# EasyEDA_H-O-A_Switch_Plug.net
KiCad netlist of a schematic drawn in EasyEDA
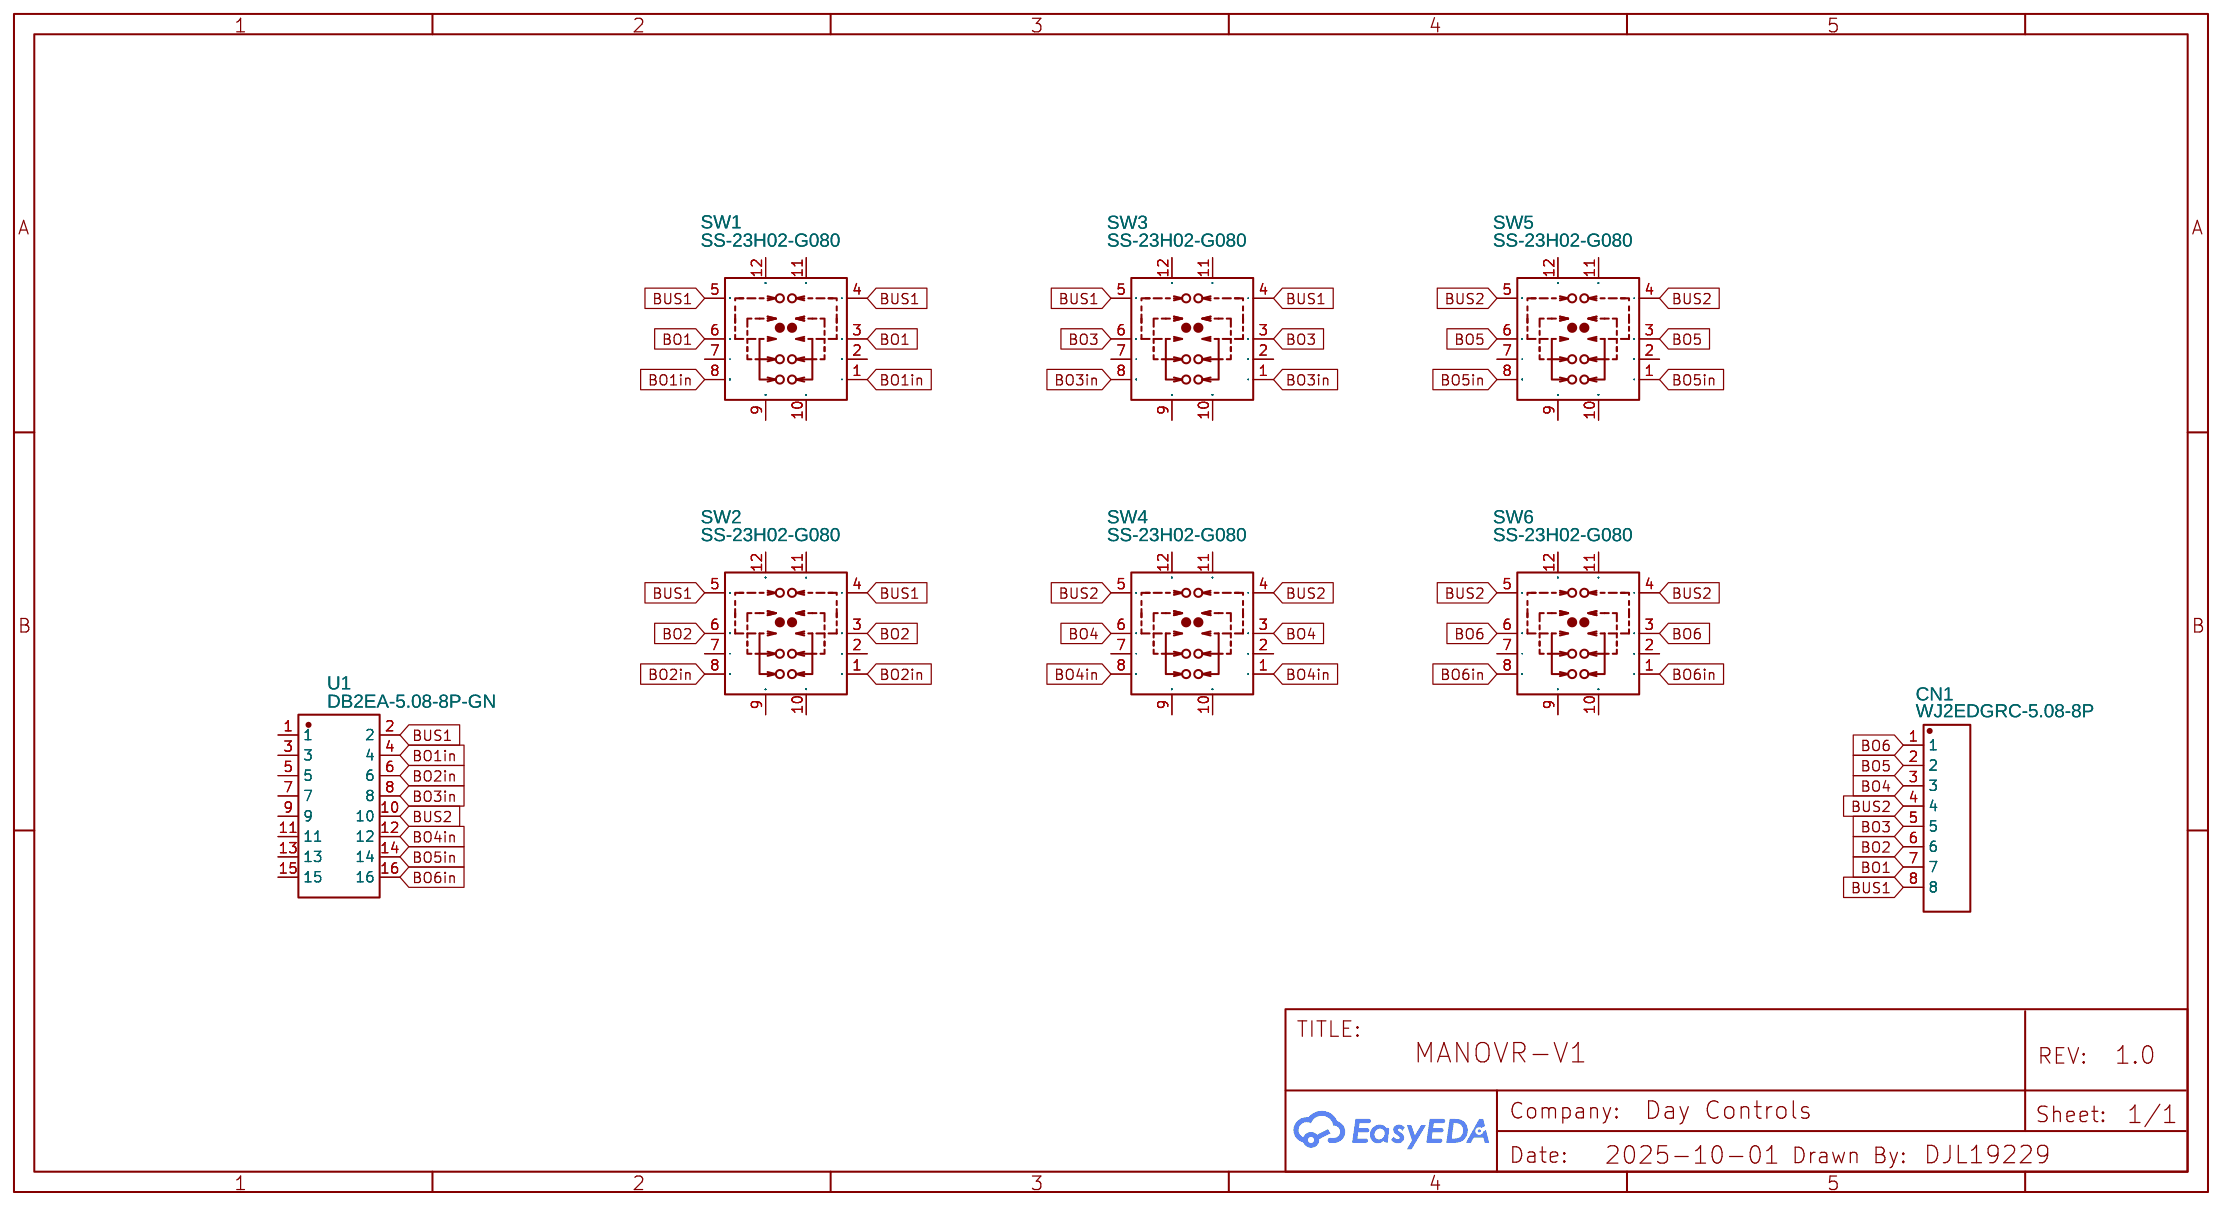
[diagram p0: schematic sheet]

(export (version "E")
  (design (tool "Eeschema 10.0.6"))
  (components
    (comp (ref "CN1")
      (value "WJ2EDGRC-5.08-8P")
      (fields (field (name "Manufacturer") "KANGNEX(康奈克斯电气)"))
      (libsource (lib "") (part "WJ2EDGRC-5.08-8P"))
    )
    (comp (ref "SW1")
      (value "SS-23H02-G080")
      (fields (field (name "Manufacturer") "G-Switch(品赞)"))
      (libsource (lib "") (part "SS-23H02-G080"))
    )
    (comp (ref "SW2")
      (value "SS-23H02-G080")
      (fields (field (name "Manufacturer") "G-Switch(品赞)"))
      (libsource (lib "") (part "SS-23H02-G080"))
    )
    (comp (ref "SW3")
      (value "SS-23H02-G080")
      (fields (field (name "Manufacturer") "G-Switch(品赞)"))
      (libsource (lib "") (part "SS-23H02-G080"))
    )
    (comp (ref "SW4")
      (value "SS-23H02-G080")
      (fields (field (name "Manufacturer") "G-Switch(品赞)"))
      (libsource (lib "") (part "SS-23H02-G080"))
    )
    (comp (ref "SW5")
      (value "SS-23H02-G080")
      (fields (field (name "Manufacturer") "G-Switch(品赞)"))
      (libsource (lib "") (part "SS-23H02-G080"))
    )
    (comp (ref "SW6")
      (value "SS-23H02-G080")
      (fields (field (name "Manufacturer") "G-Switch(品赞)"))
      (libsource (lib "") (part "SS-23H02-G080"))
    )
    (comp (ref "U1")
      (value "DB2EA-5.08-8P-GN")
      (fields (field (name "Manufacturer") "DORABO(地博电气)"))
      (libsource (lib "") (part "DB2EA-5.08-8P-GN"))
    )
  )
  (nets
    (net (code "1") (name "BO1") (class "Default")
      (node (ref "CN1") (pin "7") (pinfunction "7_7") (pintype "unspecified"))
      (node (ref "SW1") (pin "3") (pinfunction "3_3") (pintype "unspecified"))
      (node (ref "SW1") (pin "6") (pinfunction "6_6") (pintype "unspecified"))
    )
    (net (code "2") (name "BO1in") (class "Default")
      (node (ref "SW1") (pin "1") (pinfunction "1_1") (pintype "unspecified"))
      (node (ref "SW1") (pin "8") (pinfunction "8_8") (pintype "unspecified"))
      (node (ref "U1") (pin "4") (pinfunction "4_4") (pintype "unspecified"))
    )
    (net (code "3") (name "BO2") (class "Default")
      (node (ref "CN1") (pin "6") (pinfunction "6_6") (pintype "unspecified"))
      (node (ref "SW2") (pin "3") (pinfunction "3_3") (pintype "unspecified"))
      (node (ref "SW2") (pin "6") (pinfunction "6_6") (pintype "unspecified"))
    )
    (net (code "4") (name "BO2in") (class "Default")
      (node (ref "SW2") (pin "1") (pinfunction "1_1") (pintype "unspecified"))
      (node (ref "SW2") (pin "8") (pinfunction "8_8") (pintype "unspecified"))
      (node (ref "U1") (pin "6") (pinfunction "6_6") (pintype "unspecified"))
    )
    (net (code "5") (name "BO3") (class "Default")
      (node (ref "CN1") (pin "5") (pinfunction "5_5") (pintype "unspecified"))
      (node (ref "SW3") (pin "3") (pinfunction "3_3") (pintype "unspecified"))
      (node (ref "SW3") (pin "6") (pinfunction "6_6") (pintype "unspecified"))
    )
    (net (code "6") (name "BO3in") (class "Default")
      (node (ref "SW3") (pin "1") (pinfunction "1_1") (pintype "unspecified"))
      (node (ref "SW3") (pin "8") (pinfunction "8_8") (pintype "unspecified"))
      (node (ref "U1") (pin "8") (pinfunction "8_8") (pintype "unspecified"))
    )
    (net (code "7") (name "BO4") (class "Default")
      (node (ref "CN1") (pin "3") (pinfunction "3_3") (pintype "unspecified"))
      (node (ref "SW4") (pin "3") (pinfunction "3_3") (pintype "unspecified"))
      (node (ref "SW4") (pin "6") (pinfunction "6_6") (pintype "unspecified"))
    )
    (net (code "8") (name "BO4in") (class "Default")
      (node (ref "SW4") (pin "1") (pinfunction "1_1") (pintype "unspecified"))
      (node (ref "SW4") (pin "8") (pinfunction "8_8") (pintype "unspecified"))
      (node (ref "U1") (pin "12") (pinfunction "12_12") (pintype "unspecified"))
    )
    (net (code "9") (name "BO5") (class "Default")
      (node (ref "CN1") (pin "2") (pinfunction "2_2") (pintype "unspecified"))
      (node (ref "SW5") (pin "3") (pinfunction "3_3") (pintype "unspecified"))
      (node (ref "SW5") (pin "6") (pinfunction "6_6") (pintype "unspecified"))
    )
    (net (code "10") (name "BO5in") (class "Default")
      (node (ref "SW5") (pin "1") (pinfunction "1_1") (pintype "unspecified"))
      (node (ref "SW5") (pin "8") (pinfunction "8_8") (pintype "unspecified"))
      (node (ref "U1") (pin "14") (pinfunction "14_14") (pintype "unspecified"))
    )
    (net (code "11") (name "BO6") (class "Default")
      (node (ref "CN1") (pin "1") (pinfunction "1_1") (pintype "unspecified"))
      (node (ref "SW6") (pin "3") (pinfunction "3_3") (pintype "unspecified"))
      (node (ref "SW6") (pin "6") (pinfunction "6_6") (pintype "unspecified"))
    )
    (net (code "12") (name "BO6in") (class "Default")
      (node (ref "SW6") (pin "1") (pinfunction "1_1") (pintype "unspecified"))
      (node (ref "SW6") (pin "8") (pinfunction "8_8") (pintype "unspecified"))
      (node (ref "U1") (pin "16") (pinfunction "16_16") (pintype "unspecified"))
    )
    (net (code "13") (name "BUS1") (class "Default")
      (node (ref "CN1") (pin "8") (pinfunction "8_8") (pintype "unspecified"))
      (node (ref "SW1") (pin "4") (pinfunction "4_4") (pintype "unspecified"))
      (node (ref "SW1") (pin "5") (pinfunction "5_5") (pintype "unspecified"))
      (node (ref "SW2") (pin "4") (pinfunction "4_4") (pintype "unspecified"))
      (node (ref "SW2") (pin "5") (pinfunction "5_5") (pintype "unspecified"))
      (node (ref "SW3") (pin "4") (pinfunction "4_4") (pintype "unspecified"))
      (node (ref "SW3") (pin "5") (pinfunction "5_5") (pintype "unspecified"))
      (node (ref "U1") (pin "2") (pinfunction "2_2") (pintype "unspecified"))
    )
    (net (code "14") (name "BUS2") (class "Default")
      (node (ref "CN1") (pin "4") (pinfunction "4_4") (pintype "unspecified"))
      (node (ref "SW4") (pin "4") (pinfunction "4_4") (pintype "unspecified"))
      (node (ref "SW4") (pin "5") (pinfunction "5_5") (pintype "unspecified"))
      (node (ref "SW5") (pin "4") (pinfunction "4_4") (pintype "unspecified"))
      (node (ref "SW5") (pin "5") (pinfunction "5_5") (pintype "unspecified"))
      (node (ref "SW6") (pin "4") (pinfunction "4_4") (pintype "unspecified"))
      (node (ref "SW6") (pin "5") (pinfunction "5_5") (pintype "unspecified"))
      (node (ref "U1") (pin "10") (pinfunction "10_10") (pintype "unspecified"))
    )
    (net (code "15") (name "unconnected-(SW1-Pad2)") (class "Default")
      (node (ref "SW1") (pin "2") (pinfunction "2_2") (pintype "unspecified"))
    )
    (net (code "16") (name "unconnected-(SW1-Pad7)") (class "Default")
      (node (ref "SW1") (pin "7") (pinfunction "7_7") (pintype "unspecified"))
    )
    (net (code "17") (name "unconnected-(SW1-Pad9)") (class "Default")
      (node (ref "SW1") (pin "9") (pinfunction "9_9") (pintype "unspecified"))
    )
    (net (code "18") (name "unconnected-(SW1-Pad10)") (class "Default")
      (node (ref "SW1") (pin "10") (pinfunction "10_10") (pintype "unspecified"))
    )
    (net (code "19") (name "unconnected-(SW1-Pad11)") (class "Default")
      (node (ref "SW1") (pin "11") (pinfunction "11_11") (pintype "unspecified"))
    )
    (net (code "20") (name "unconnected-(SW1-Pad12)") (class "Default")
      (node (ref "SW1") (pin "12") (pinfunction "12_12") (pintype "unspecified"))
    )
    (net (code "21") (name "unconnected-(SW2-Pad2)") (class "Default")
      (node (ref "SW2") (pin "2") (pinfunction "2_2") (pintype "unspecified"))
    )
    (net (code "22") (name "unconnected-(SW2-Pad7)") (class "Default")
      (node (ref "SW2") (pin "7") (pinfunction "7_7") (pintype "unspecified"))
    )
    (net (code "23") (name "unconnected-(SW2-Pad9)") (class "Default")
      (node (ref "SW2") (pin "9") (pinfunction "9_9") (pintype "unspecified"))
    )
    (net (code "24") (name "unconnected-(SW2-Pad10)") (class "Default")
      (node (ref "SW2") (pin "10") (pinfunction "10_10") (pintype "unspecified"))
    )
    (net (code "25") (name "unconnected-(SW2-Pad11)") (class "Default")
      (node (ref "SW2") (pin "11") (pinfunction "11_11") (pintype "unspecified"))
    )
    (net (code "26") (name "unconnected-(SW2-Pad12)") (class "Default")
      (node (ref "SW2") (pin "12") (pinfunction "12_12") (pintype "unspecified"))
    )
    (net (code "27") (name "unconnected-(SW3-Pad2)") (class "Default")
      (node (ref "SW3") (pin "2") (pinfunction "2_2") (pintype "unspecified"))
    )
    (net (code "28") (name "unconnected-(SW3-Pad7)") (class "Default")
      (node (ref "SW3") (pin "7") (pinfunction "7_7") (pintype "unspecified"))
    )
    (net (code "29") (name "unconnected-(SW3-Pad9)") (class "Default")
      (node (ref "SW3") (pin "9") (pinfunction "9_9") (pintype "unspecified"))
    )
    (net (code "30") (name "unconnected-(SW3-Pad10)") (class "Default")
      (node (ref "SW3") (pin "10") (pinfunction "10_10") (pintype "unspecified"))
    )
    (net (code "31") (name "unconnected-(SW3-Pad11)") (class "Default")
      (node (ref "SW3") (pin "11") (pinfunction "11_11") (pintype "unspecified"))
    )
    (net (code "32") (name "unconnected-(SW3-Pad12)") (class "Default")
      (node (ref "SW3") (pin "12") (pinfunction "12_12") (pintype "unspecified"))
    )
    (net (code "33") (name "unconnected-(SW4-Pad2)") (class "Default")
      (node (ref "SW4") (pin "2") (pinfunction "2_2") (pintype "unspecified"))
    )
    (net (code "34") (name "unconnected-(SW4-Pad7)") (class "Default")
      (node (ref "SW4") (pin "7") (pinfunction "7_7") (pintype "unspecified"))
    )
    (net (code "35") (name "unconnected-(SW4-Pad9)") (class "Default")
      (node (ref "SW4") (pin "9") (pinfunction "9_9") (pintype "unspecified"))
    )
    (net (code "36") (name "unconnected-(SW4-Pad10)") (class "Default")
      (node (ref "SW4") (pin "10") (pinfunction "10_10") (pintype "unspecified"))
    )
    (net (code "37") (name "unconnected-(SW4-Pad11)") (class "Default")
      (node (ref "SW4") (pin "11") (pinfunction "11_11") (pintype "unspecified"))
    )
    (net (code "38") (name "unconnected-(SW4-Pad12)") (class "Default")
      (node (ref "SW4") (pin "12") (pinfunction "12_12") (pintype "unspecified"))
    )
    (net (code "39") (name "unconnected-(SW5-Pad2)") (class "Default")
      (node (ref "SW5") (pin "2") (pinfunction "2_2") (pintype "unspecified"))
    )
    (net (code "40") (name "unconnected-(SW5-Pad7)") (class "Default")
      (node (ref "SW5") (pin "7") (pinfunction "7_7") (pintype "unspecified"))
    )
    (net (code "41") (name "unconnected-(SW5-Pad9)") (class "Default")
      (node (ref "SW5") (pin "9") (pinfunction "9_9") (pintype "unspecified"))
    )
    (net (code "42") (name "unconnected-(SW5-Pad10)") (class "Default")
      (node (ref "SW5") (pin "10") (pinfunction "10_10") (pintype "unspecified"))
    )
    (net (code "43") (name "unconnected-(SW5-Pad11)") (class "Default")
      (node (ref "SW5") (pin "11") (pinfunction "11_11") (pintype "unspecified"))
    )
    (net (code "44") (name "unconnected-(SW5-Pad12)") (class "Default")
      (node (ref "SW5") (pin "12") (pinfunction "12_12") (pintype "unspecified"))
    )
    (net (code "45") (name "unconnected-(SW6-Pad2)") (class "Default")
      (node (ref "SW6") (pin "2") (pinfunction "2_2") (pintype "unspecified"))
    )
    (net (code "46") (name "unconnected-(SW6-Pad7)") (class "Default")
      (node (ref "SW6") (pin "7") (pinfunction "7_7") (pintype "unspecified"))
    )
    (net (code "47") (name "unconnected-(SW6-Pad9)") (class "Default")
      (node (ref "SW6") (pin "9") (pinfunction "9_9") (pintype "unspecified"))
    )
    (net (code "48") (name "unconnected-(SW6-Pad10)") (class "Default")
      (node (ref "SW6") (pin "10") (pinfunction "10_10") (pintype "unspecified"))
    )
    (net (code "49") (name "unconnected-(SW6-Pad11)") (class "Default")
      (node (ref "SW6") (pin "11") (pinfunction "11_11") (pintype "unspecified"))
    )
    (net (code "50") (name "unconnected-(SW6-Pad12)") (class "Default")
      (node (ref "SW6") (pin "12") (pinfunction "12_12") (pintype "unspecified"))
    )
    (net (code "51") (name "unconnected-(U1-Pad1)") (class "Default")
      (node (ref "U1") (pin "1") (pinfunction "1_1") (pintype "unspecified"))
    )
    (net (code "52") (name "unconnected-(U1-Pad3)") (class "Default")
      (node (ref "U1") (pin "3") (pinfunction "3_3") (pintype "unspecified"))
    )
    (net (code "53") (name "unconnected-(U1-Pad5)") (class "Default")
      (node (ref "U1") (pin "5") (pinfunction "5_5") (pintype "unspecified"))
    )
    (net (code "54") (name "unconnected-(U1-Pad7)") (class "Default")
      (node (ref "U1") (pin "7") (pinfunction "7_7") (pintype "unspecified"))
    )
    (net (code "55") (name "unconnected-(U1-Pad9)") (class "Default")
      (node (ref "U1") (pin "9") (pinfunction "9_9") (pintype "unspecified"))
    )
    (net (code "56") (name "unconnected-(U1-Pad11)") (class "Default")
      (node (ref "U1") (pin "11") (pinfunction "11_11") (pintype "unspecified"))
    )
    (net (code "57") (name "unconnected-(U1-Pad13)") (class "Default")
      (node (ref "U1") (pin "13") (pinfunction "13_13") (pintype "unspecified"))
    )
    (net (code "58") (name "unconnected-(U1-Pad15)") (class "Default")
      (node (ref "U1") (pin "15") (pinfunction "15_15") (pintype "unspecified"))
    )
  )
)
